# PRC-1605-AFC.net
KiCad netlist of a schematic drawn in EAGLE
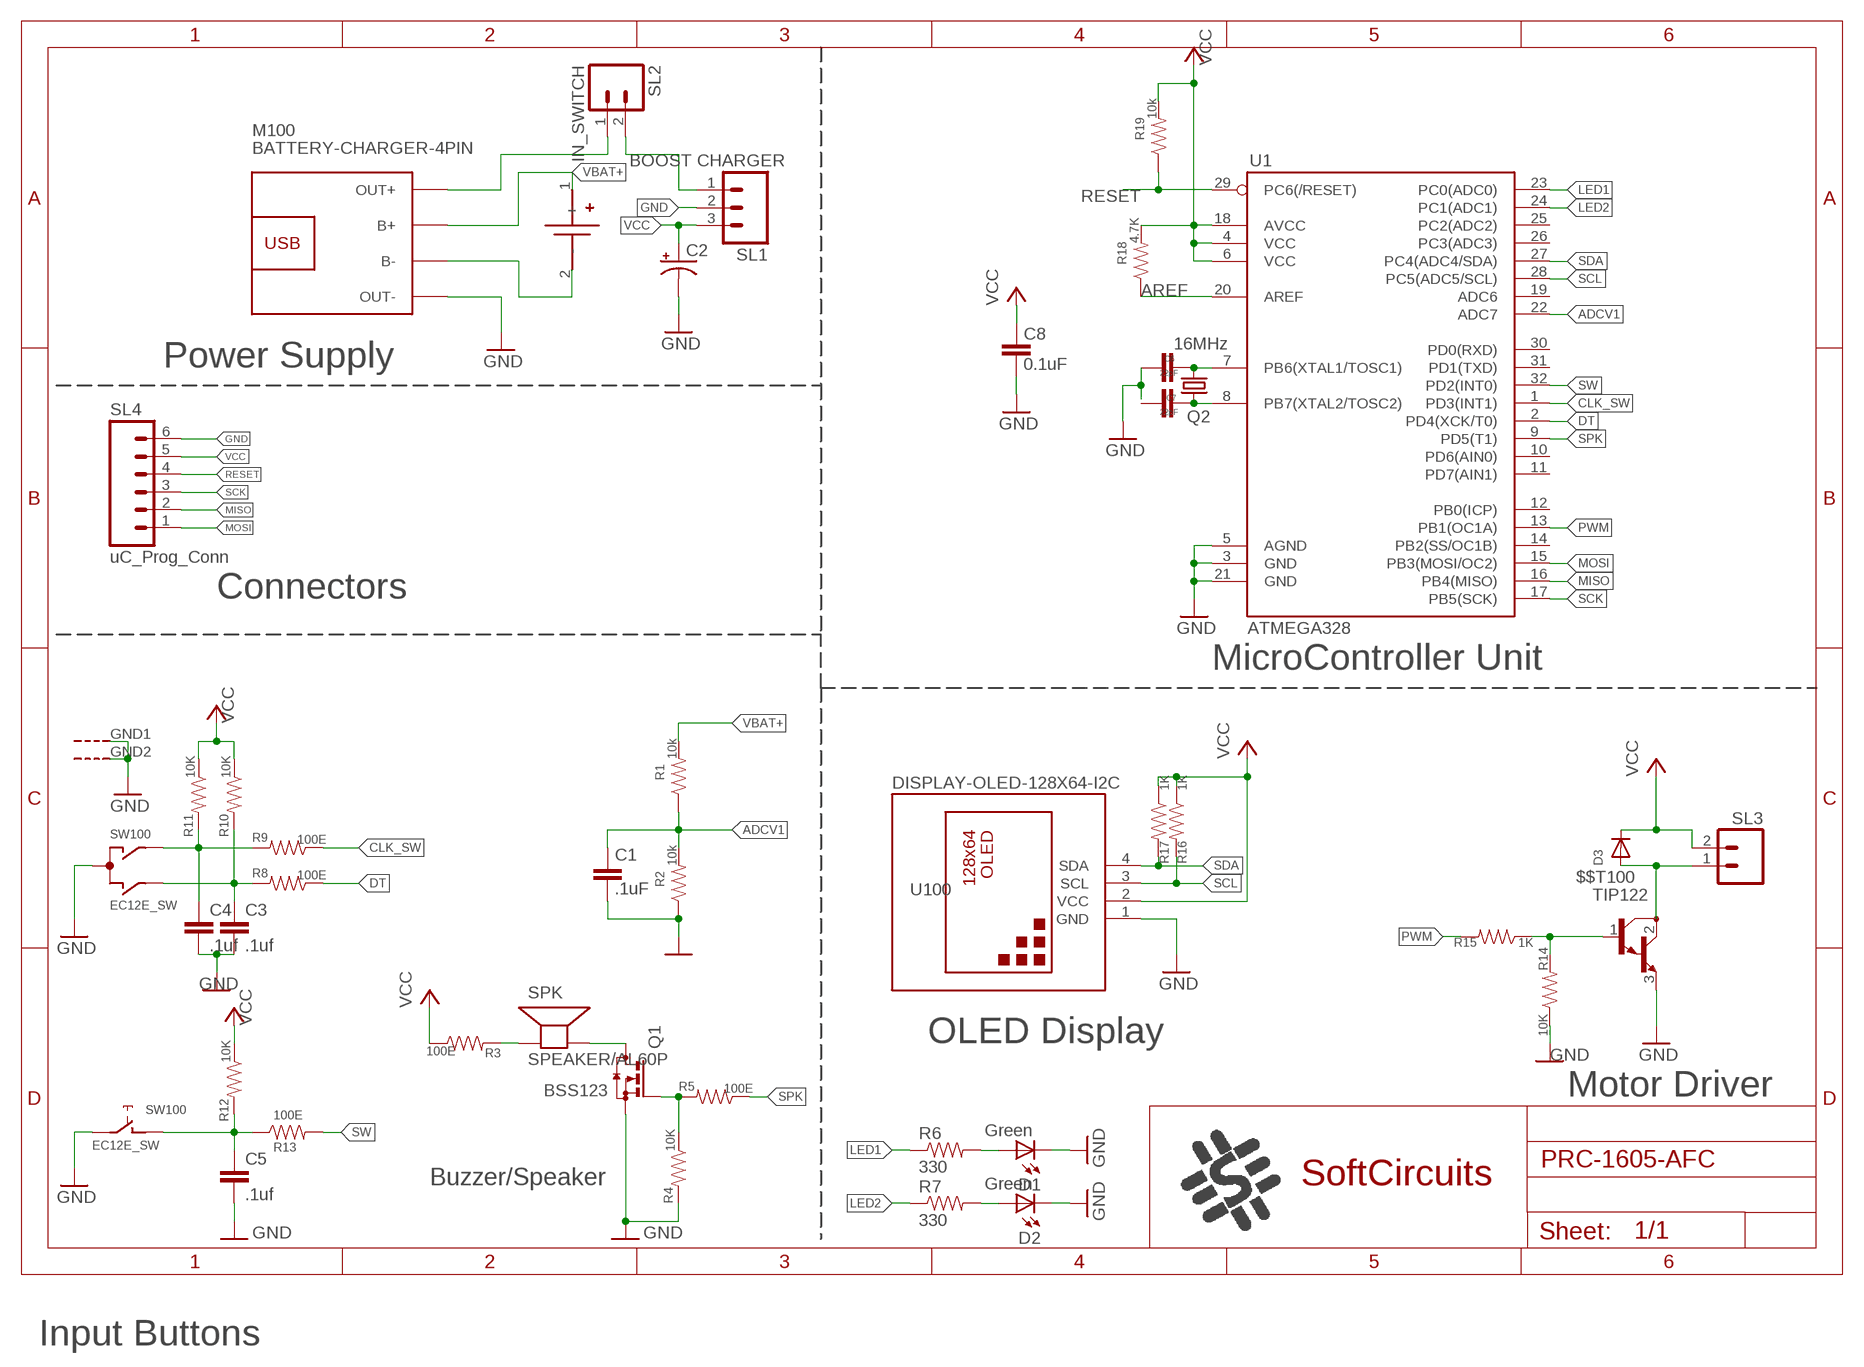
[diagram p0: schematic, sheet 1]

(export (version "E")
  (design (tool "Eeschema 10.0.6"))
  (components
    (comp (ref "$$T100")
      (value "TIP122")
      (footprint "eagle-import:TO220")
      (libsource (lib "eagle-import") (part "TIP122"))
    )
    (comp (ref "C1")
      (value ".1uF")
      (footprint "eagle-import:C1206")
      (libsource (lib "eagle-import") (part "C-EUC1206"))
    )
    (comp (ref "C2")
      (value "CPOL-USE2.5-7")
      (footprint "eagle-import:E2,5-7")
      (libsource (lib "eagle-import") (part "CPOL-USE2.5-7"))
    )
    (comp (ref "C3")
      (value ".1uf")
      (footprint "eagle-import:C1206")
      (libsource (lib "eagle-import") (part "C-EUC1206"))
    )
    (comp (ref "C4")
      (value ".1uf")
      (footprint "eagle-import:C1206")
      (libsource (lib "eagle-import") (part "C-EUC1206"))
    )
    (comp (ref "C5")
      (value ".1uf")
      (footprint "eagle-import:C1206")
      (libsource (lib "eagle-import") (part "C-EUC1206"))
    )
    (comp (ref "C6")
      (value "22pF")
      (footprint "eagle-import:C1206")
      (libsource (lib "eagle-import") (part "C-EUC1206"))
    )
    (comp (ref "C7")
      (value "22pF")
      (footprint "eagle-import:C1206")
      (libsource (lib "eagle-import") (part "C-EUC1206"))
    )
    (comp (ref "C8")
      (value "0.1uF")
      (footprint "eagle-import:C1206")
      (libsource (lib "eagle-import") (part "C-EUC1206"))
    )
    (comp (ref "D1")
      (value "Green")
      (footprint "eagle-import:CHIPLED_1206")
      (libsource (lib "eagle-import") (part "LEDCHIPLED_1206"))
    )
    (comp (ref "D2")
      (value "Green")
      (footprint "eagle-import:CHIPLED_1206")
      (libsource (lib "eagle-import") (part "LEDCHIPLED_1206"))
    )
    (comp (ref "D3")
      (value "DIODESMA")
      (footprint "eagle-import:SMADIODE")
      (libsource (lib "eagle-import") (part "DIODESMA"))
    )
    (comp (ref "LOGO100")
      (value "SC_LOGO")
      (footprint "eagle-import:SC_LOGO")
      (libsource (lib "eagle-import") (part "SC_LOGO"))
    )
    (comp (ref "M100")
      (value "BATTERY-CHARGER-4PIN")
      (footprint "eagle-import:BATTERY-CHARGER-LI-4PIN")
      (libsource (lib "eagle-import") (part "BATTERY-CHARGER-4PIN"))
    )
    (comp (ref "Q1")
      (value "BSS123")
      (footprint "eagle-import:SOT23")
      (libsource (lib "eagle-import") (part "BSS123"))
    )
    (comp (ref "Q2")
      (value "16MHz")
      (footprint "eagle-import:HC49UP")
      (libsource (lib "eagle-import") (part "CRYSTALHC49UP"))
    )
    (comp (ref "R1")
      (value "10k")
      (footprint "eagle-import:1206")
      (libsource (lib "eagle-import") (part "RESISTOR1206"))
    )
    (comp (ref "R2")
      (value "10k")
      (footprint "eagle-import:1206")
      (libsource (lib "eagle-import") (part "RESISTOR1206"))
    )
    (comp (ref "R3")
      (value "100E")
      (footprint "eagle-import:1206")
      (libsource (lib "eagle-import") (part "RESISTOR1206"))
    )
    (comp (ref "R4")
      (value "10K")
      (footprint "eagle-import:1206")
      (libsource (lib "eagle-import") (part "RESISTOR1206"))
    )
    (comp (ref "R5")
      (value "100E")
      (footprint "eagle-import:1206")
      (libsource (lib "eagle-import") (part "RESISTOR1206"))
    )
    (comp (ref "R6")
      (value "330")
      (footprint "eagle-import:1206")
      (libsource (lib "eagle-import") (part "RESISTOR1206"))
    )
    (comp (ref "R7")
      (value "330")
      (footprint "eagle-import:1206")
      (libsource (lib "eagle-import") (part "RESISTOR1206"))
    )
    (comp (ref "R8")
      (value "100E")
      (footprint "eagle-import:1206")
      (libsource (lib "eagle-import") (part "RESISTOR1206"))
    )
    (comp (ref "R9")
      (value "100E")
      (footprint "eagle-import:1206")
      (libsource (lib "eagle-import") (part "RESISTOR1206"))
    )
    (comp (ref "R10")
      (value "10K")
      (footprint "eagle-import:1206")
      (libsource (lib "eagle-import") (part "RESISTOR1206"))
    )
    (comp (ref "R11")
      (value "10K")
      (footprint "eagle-import:1206")
      (libsource (lib "eagle-import") (part "RESISTOR1206"))
    )
    (comp (ref "R12")
      (value "10K")
      (footprint "eagle-import:1206")
      (libsource (lib "eagle-import") (part "RESISTOR1206"))
    )
    (comp (ref "R13")
      (value "100E")
      (footprint "eagle-import:1206")
      (libsource (lib "eagle-import") (part "RESISTOR1206"))
    )
    (comp (ref "R14")
      (value "10K")
      (footprint "eagle-import:1206")
      (libsource (lib "eagle-import") (part "RESISTOR1206"))
    )
    (comp (ref "R15")
      (value "1K")
      (footprint "eagle-import:1206")
      (libsource (lib "eagle-import") (part "RESISTOR1206"))
    )
    (comp (ref "R16")
      (value "1K")
      (footprint "eagle-import:1206")
      (libsource (lib "eagle-import") (part "RESISTOR1206"))
    )
    (comp (ref "R17")
      (value "1K")
      (footprint "eagle-import:1206")
      (libsource (lib "eagle-import") (part "RESISTOR1206"))
    )
    (comp (ref "R18")
      (value "4.7K")
      (footprint "eagle-import:1206")
      (libsource (lib "eagle-import") (part "RESISTOR1206"))
    )
    (comp (ref "R19")
      (value "10k")
      (footprint "eagle-import:1206")
      (libsource (lib "eagle-import") (part "RESISTOR1206"))
    )
    (comp (ref "SL1")
      (value "BOOST CHARGER")
      (footprint "eagle-import:03P")
      (libsource (lib "eagle-import") (part "M03"))
    )
    (comp (ref "SL2")
      (value "IN_SWITCH")
      (footprint "eagle-import:02P")
      (libsource (lib "eagle-import") (part "M02"))
    )
    (comp (ref "SL3")
      (value "M02")
      (footprint "eagle-import:02P")
      (libsource (lib "eagle-import") (part "M02"))
    )
    (comp (ref "SL4")
      (value "uC_Prog_Conn")
      (footprint "eagle-import:06P")
      (libsource (lib "eagle-import") (part "M06"))
    )
    (comp (ref "SPK")
      (value "SPEAKER/AL60P")
      (footprint "eagle-import:AL60P")
      (libsource (lib "eagle-import") (part "SPEAKER/AL60P"))
    )
    (comp (ref "SW100")
      (value "EC12E_SW")
      (footprint "eagle-import:ALPS_EC12E_SW")
      (fields (field (name "MPN") "EC12E2424407"))
      (libsource (lib "eagle-import") (part "EC12E_SW"))
    )
    (comp (ref "U$2")
      (value "BLOSSOM-BLM-18650-1PCS")
      (footprint "eagle-import:BLOSSOM-BLM-18650-1PCS")
      (libsource (lib "eagle-import") (part "BLOSSOM-BLM-18650-1PCS"))
    )
    (comp (ref "U1")
      (value "ATMEGA328")
      (footprint "eagle-import:TQFP32-08")
      (libsource (lib "eagle-import") (part "ATMEGA168"))
    )
    (comp (ref "U100")
      (value "DISPLAY-OLED-128X64-I2C")
      (footprint "eagle-import:DISPLAY-OLED-128X64-I2C")
      (libsource (lib "eagle-import") (part "DISPLAY-OLED-128X64-I2C"))
    )
  )
  (nets
    (net (code "1") (name "/AREF") (class "Default")
      (node (ref "R18") (pin "1") (pinfunction "1_1") (pintype "passive"))
      (node (ref "U1") (pin "20") (pinfunction "AREF_20") (pintype "bidirectional"))
    )
    (net (code "2") (name "ADCV1") (class "Default")
      (node (ref "C1") (pin "1") (pinfunction "1_1") (pintype "passive"))
      (node (ref "R1") (pin "1") (pinfunction "1_1") (pintype "passive"))
      (node (ref "R2") (pin "2") (pinfunction "2_2") (pintype "passive"))
      (node (ref "U1") (pin "22") (pinfunction "ADC7_22") (pintype "bidirectional"))
    )
    (net (code "3") (name "CLK_SW") (class "Default")
      (node (ref "R9") (pin "1") (pinfunction "1_1") (pintype "passive"))
      (node (ref "U1") (pin "1") (pinfunction "PD3(INT1)_1") (pintype "bidirectional"))
    )
    (net (code "4") (name "DT") (class "Default")
      (node (ref "R8") (pin "1") (pinfunction "1_1") (pintype "passive"))
      (node (ref "U1") (pin "2") (pinfunction "PD4(XCK/T0)_2") (pintype "bidirectional"))
    )
    (net (code "5") (name "GND") (class "Default")
      (node (ref "$$T100") (pin "3") (pinfunction "E_3") (pintype "passive"))
      (node (ref "C1") (pin "2") (pinfunction "2_2") (pintype "passive"))
      (node (ref "C2") (pin "-") (pinfunction "-_-") (pintype "passive"))
      (node (ref "C3") (pin "2") (pinfunction "2_2") (pintype "passive"))
      (node (ref "C4") (pin "2") (pinfunction "2_2") (pintype "passive"))
      (node (ref "C5") (pin "2") (pinfunction "2_2") (pintype "passive"))
      (node (ref "C6") (pin "2") (pinfunction "2_2") (pintype "passive"))
      (node (ref "C7") (pin "2") (pinfunction "2_2") (pintype "passive"))
      (node (ref "C8") (pin "1") (pinfunction "1_1") (pintype "passive"))
      (node (ref "D1") (pin "C") (pinfunction "C_C") (pintype "passive"))
      (node (ref "D2") (pin "C") (pinfunction "C_C") (pintype "passive"))
      (node (ref "M100") (pin "OUT-") (pinfunction "OUT-_OUT-") (pintype "bidirectional"))
      (node (ref "Q1") (pin "2") (pinfunction "S_2") (pintype "passive"))
      (node (ref "R14") (pin "1") (pinfunction "1_1") (pintype "passive"))
      (node (ref "R2") (pin "1") (pinfunction "1_1") (pintype "passive"))
      (node (ref "R4") (pin "2") (pinfunction "2_2") (pintype "passive"))
      (node (ref "SL1") (pin "2") (pinfunction "2_2") (pintype "passive"))
      (node (ref "SL4") (pin "6") (pinfunction "6_6") (pintype "passive"))
      (node (ref "SW100") (pin "C") (pinfunction "C_C") (pintype "passive"))
      (node (ref "SW100") (pin "E") (pinfunction "2_E") (pintype "passive"))
      (node (ref "SW100") (pin "GND1") (pinfunction "G_GND1") (pintype "passive"))
      (node (ref "SW100") (pin "GND2") (pinfunction "G_GND2") (pintype "passive"))
      (node (ref "U1") (pin "21") (pinfunction "GND_21") (pintype "bidirectional"))
      (node (ref "U1") (pin "3") (pinfunction "GND_3") (pintype "bidirectional"))
      (node (ref "U1") (pin "5") (pinfunction "AGND_5") (pintype "bidirectional"))
      (node (ref "U100") (pin "1") (pinfunction "GND_1") (pintype "power_in"))
    )
    (net (code "6") (name "LED1") (class "Default")
      (node (ref "R6") (pin "1") (pinfunction "1_1") (pintype "passive"))
      (node (ref "U1") (pin "23") (pinfunction "PC0(ADC0)_23") (pintype "bidirectional"))
    )
    (net (code "7") (name "LED2") (class "Default")
      (node (ref "R7") (pin "1") (pinfunction "1_1") (pintype "passive"))
      (node (ref "U1") (pin "24") (pinfunction "PC1(ADC1)_24") (pintype "bidirectional"))
    )
    (net (code "8") (name "MISO") (class "Default")
      (node (ref "SL4") (pin "2") (pinfunction "2_2") (pintype "passive"))
      (node (ref "U1") (pin "16") (pinfunction "PB4(MISO)_16") (pintype "bidirectional"))
    )
    (net (code "9") (name "MOSI") (class "Default")
      (node (ref "SL4") (pin "1") (pinfunction "1_1") (pintype "passive"))
      (node (ref "U1") (pin "15") (pinfunction "PB3(MOSI/OC2)_15") (pintype "bidirectional"))
    )
    (net (code "10") (name "Net-($$T100-B)") (class "Default")
      (node (ref "$$T100") (pin "1") (pinfunction "B_1") (pintype "passive"))
      (node (ref "R14") (pin "2") (pinfunction "2_2") (pintype "passive"))
      (node (ref "R15") (pin "1") (pinfunction "1_1") (pintype "passive"))
    )
    (net (code "11") (name "Net-($$T100-C)") (class "Default")
      (node (ref "$$T100") (pin "2") (pinfunction "C_2") (pintype "passive"))
      (node (ref "D3") (pin "A") (pinfunction "A_A") (pintype "passive"))
      (node (ref "SL3") (pin "1") (pinfunction "1_1") (pintype "passive"))
    )
    (net (code "12") (name "Net-(C3-Pad1)") (class "Default")
      (node (ref "C3") (pin "1") (pinfunction "1_1") (pintype "passive"))
      (node (ref "R10") (pin "2") (pinfunction "2_2") (pintype "passive"))
      (node (ref "R8") (pin "2") (pinfunction "2_2") (pintype "passive"))
      (node (ref "SW100") (pin "B") (pinfunction "B_B") (pintype "passive"))
    )
    (net (code "13") (name "Net-(C4-Pad1)") (class "Default")
      (node (ref "C4") (pin "1") (pinfunction "1_1") (pintype "passive"))
      (node (ref "R11") (pin "2") (pinfunction "2_2") (pintype "passive"))
      (node (ref "R9") (pin "2") (pinfunction "2_2") (pintype "passive"))
      (node (ref "SW100") (pin "A") (pinfunction "A_A") (pintype "passive"))
    )
    (net (code "14") (name "Net-(D1-PadA)") (class "Default")
      (node (ref "D1") (pin "A") (pinfunction "A_A") (pintype "passive"))
      (node (ref "R6") (pin "2") (pinfunction "2_2") (pintype "passive"))
    )
    (net (code "15") (name "Net-(D2-PadA)") (class "Default")
      (node (ref "D2") (pin "A") (pinfunction "A_A") (pintype "passive"))
      (node (ref "R7") (pin "2") (pinfunction "2_2") (pintype "passive"))
    )
    (net (code "16") (name "Net-(M100-PadOUT+)") (class "Default")
      (node (ref "M100") (pin "OUT+") (pinfunction "OUT+_OUT+") (pintype "bidirectional"))
      (node (ref "SL2") (pin "1") (pinfunction "1_1") (pintype "passive"))
    )
    (net (code "17") (name "Net-(Q1-D)") (class "Default")
      (node (ref "Q1") (pin "3") (pinfunction "D_3") (pintype "passive"))
      (node (ref "SPK") (pin "2") (pinfunction "-_2") (pintype "passive"))
    )
    (net (code "18") (name "Net-(Q1-G)") (class "Default")
      (node (ref "Q1") (pin "1") (pinfunction "G_1") (pintype "passive"))
      (node (ref "R4") (pin "1") (pinfunction "1_1") (pintype "passive"))
      (node (ref "R5") (pin "2") (pinfunction "2_2") (pintype "passive"))
    )
    (net (code "19") (name "Net-(SL1-Pad1)") (class "Default")
      (node (ref "SL1") (pin "1") (pinfunction "1_1") (pintype "passive"))
      (node (ref "SL2") (pin "2") (pinfunction "2_2") (pintype "passive"))
    )
    (net (code "20") (name "Net-(SPK-+)") (class "Default")
      (node (ref "R3") (pin "2") (pinfunction "2_2") (pintype "passive"))
      (node (ref "SPK") (pin "1") (pinfunction "+_1") (pintype "passive"))
    )
    (net (code "21") (name "Net-(SW100B-1)") (class "Default")
      (node (ref "C5") (pin "1") (pinfunction "1_1") (pintype "passive"))
      (node (ref "R12") (pin "2") (pinfunction "2_2") (pintype "passive"))
      (node (ref "R13") (pin "1") (pinfunction "1_1") (pintype "passive"))
      (node (ref "SW100") (pin "D") (pinfunction "1_D") (pintype "passive"))
    )
    (net (code "22") (name "Net-(U$2--)") (class "Default")
      (node (ref "M100") (pin "B-") (pinfunction "B-_B-") (pintype "bidirectional"))
      (node (ref "U$2") (pin "2") (pinfunction "-_2") (pintype "bidirectional"))
    )
    (net (code "23") (name "Net-(U1-PB6(XTAL1{slash}TOSC1))") (class "Default")
      (node (ref "C6") (pin "1") (pinfunction "1_1") (pintype "passive"))
      (node (ref "Q2") (pin "2") (pinfunction "2_2") (pintype "passive"))
      (node (ref "U1") (pin "7") (pinfunction "PB6(XTAL1/TOSC1)_7") (pintype "bidirectional"))
    )
    (net (code "24") (name "Net-(U1-PB7(XTAL2{slash}TOSC2))") (class "Default")
      (node (ref "C7") (pin "1") (pinfunction "1_1") (pintype "passive"))
      (node (ref "Q2") (pin "1") (pinfunction "1_1") (pintype "passive"))
      (node (ref "U1") (pin "8") (pinfunction "PB7(XTAL2/TOSC2)_8") (pintype "bidirectional"))
    )
    (net (code "25") (name "PWM") (class "Default")
      (node (ref "R15") (pin "2") (pinfunction "2_2") (pintype "passive"))
      (node (ref "U1") (pin "13") (pinfunction "PB1(OC1A)_13") (pintype "bidirectional"))
    )
    (net (code "26") (name "RESET") (class "Default")
      (node (ref "R19") (pin "1") (pinfunction "1_1") (pintype "passive"))
      (node (ref "SL4") (pin "4") (pinfunction "4_4") (pintype "passive"))
      (node (ref "U1") (pin "29") (pinfunction "PC6(/RESET)_29") (pintype "bidirectional"))
    )
    (net (code "27") (name "SCK") (class "Default")
      (node (ref "SL4") (pin "3") (pinfunction "3_3") (pintype "passive"))
      (node (ref "U1") (pin "17") (pinfunction "PB5(SCK)_17") (pintype "bidirectional"))
    )
    (net (code "28") (name "SCL") (class "Default")
      (node (ref "R16") (pin "2") (pinfunction "2_2") (pintype "passive"))
      (node (ref "U1") (pin "28") (pinfunction "PC5(ADC5/SCL)_28") (pintype "bidirectional"))
      (node (ref "U100") (pin "3") (pinfunction "SCL_3") (pintype "bidirectional"))
    )
    (net (code "29") (name "SDA") (class "Default")
      (node (ref "R17") (pin "2") (pinfunction "2_2") (pintype "passive"))
      (node (ref "U1") (pin "27") (pinfunction "PC4(ADC4/SDA)_27") (pintype "bidirectional"))
      (node (ref "U100") (pin "4") (pinfunction "SDA_4") (pintype "bidirectional"))
    )
    (net (code "30") (name "SPK") (class "Default")
      (node (ref "R5") (pin "1") (pinfunction "1_1") (pintype "passive"))
      (node (ref "U1") (pin "9") (pinfunction "PD5(T1)_9") (pintype "bidirectional"))
    )
    (net (code "31") (name "SW") (class "Default")
      (node (ref "R13") (pin "2") (pinfunction "2_2") (pintype "passive"))
      (node (ref "U1") (pin "32") (pinfunction "PD2(INT0)_32") (pintype "bidirectional"))
    )
    (net (code "32") (name "VBAT+") (class "Default")
      (node (ref "M100") (pin "B+") (pinfunction "B+_B+") (pintype "bidirectional"))
      (node (ref "R1") (pin "2") (pinfunction "2_2") (pintype "passive"))
      (node (ref "U$2") (pin "1") (pinfunction "+_1") (pintype "bidirectional"))
    )
    (net (code "33") (name "VCC") (class "Default")
      (node (ref "C2") (pin "+") (pinfunction "+_+") (pintype "passive"))
      (node (ref "C8") (pin "2") (pinfunction "2_2") (pintype "passive"))
      (node (ref "D3") (pin "C") (pinfunction "C_C") (pintype "passive"))
      (node (ref "R10") (pin "1") (pinfunction "1_1") (pintype "passive"))
      (node (ref "R11") (pin "1") (pinfunction "1_1") (pintype "passive"))
      (node (ref "R12") (pin "1") (pinfunction "1_1") (pintype "passive"))
      (node (ref "R16") (pin "1") (pinfunction "1_1") (pintype "passive"))
      (node (ref "R17") (pin "1") (pinfunction "1_1") (pintype "passive"))
      (node (ref "R18") (pin "2") (pinfunction "2_2") (pintype "passive"))
      (node (ref "R19") (pin "2") (pinfunction "2_2") (pintype "passive"))
      (node (ref "R3") (pin "1") (pinfunction "1_1") (pintype "passive"))
      (node (ref "SL1") (pin "3") (pinfunction "3_3") (pintype "passive"))
      (node (ref "SL3") (pin "2") (pinfunction "2_2") (pintype "passive"))
      (node (ref "SL4") (pin "5") (pinfunction "5_5") (pintype "passive"))
      (node (ref "U1") (pin "18") (pinfunction "AVCC_18") (pintype "bidirectional"))
      (node (ref "U1") (pin "4") (pinfunction "VCC_4") (pintype "bidirectional"))
      (node (ref "U1") (pin "6") (pinfunction "VCC_6") (pintype "bidirectional"))
      (node (ref "U100") (pin "2") (pinfunction "VCC_2") (pintype "power_in"))
    )
    (net (code "34") (name "unconnected-(U1-ADC6-Pad19)") (class "Default")
      (node (ref "U1") (pin "19") (pinfunction "ADC6_19") (pintype "bidirectional"))
    )
    (net (code "35") (name "unconnected-(U1-PB0(ICP)-Pad12)") (class "Default")
      (node (ref "U1") (pin "12") (pinfunction "PB0(ICP)_12") (pintype "bidirectional"))
    )
    (net (code "36") (name "unconnected-(U1-PB2(SS{slash}OC1B)-Pad14)") (class "Default")
      (node (ref "U1") (pin "14") (pinfunction "PB2(SS/OC1B)_14") (pintype "bidirectional"))
    )
    (net (code "37") (name "unconnected-(U1-PC2(ADC2)-Pad25)") (class "Default")
      (node (ref "U1") (pin "25") (pinfunction "PC2(ADC2)_25") (pintype "bidirectional"))
    )
    (net (code "38") (name "unconnected-(U1-PC3(ADC3)-Pad26)") (class "Default")
      (node (ref "U1") (pin "26") (pinfunction "PC3(ADC3)_26") (pintype "bidirectional"))
    )
    (net (code "39") (name "unconnected-(U1-PD0(RXD)-Pad30)") (class "Default")
      (node (ref "U1") (pin "30") (pinfunction "PD0(RXD)_30") (pintype "bidirectional"))
    )
    (net (code "40") (name "unconnected-(U1-PD1(TXD)-Pad31)") (class "Default")
      (node (ref "U1") (pin "31") (pinfunction "PD1(TXD)_31") (pintype "bidirectional"))
    )
    (net (code "41") (name "unconnected-(U1-PD6(AIN0)-Pad10)") (class "Default")
      (node (ref "U1") (pin "10") (pinfunction "PD6(AIN0)_10") (pintype "bidirectional"))
    )
    (net (code "42") (name "unconnected-(U1-PD7(AIN1)-Pad11)") (class "Default")
      (node (ref "U1") (pin "11") (pinfunction "PD7(AIN1)_11") (pintype "bidirectional"))
    )
  )
)
